# Wein.net
KiCad netlist of a schematic drawn in Altium Designer
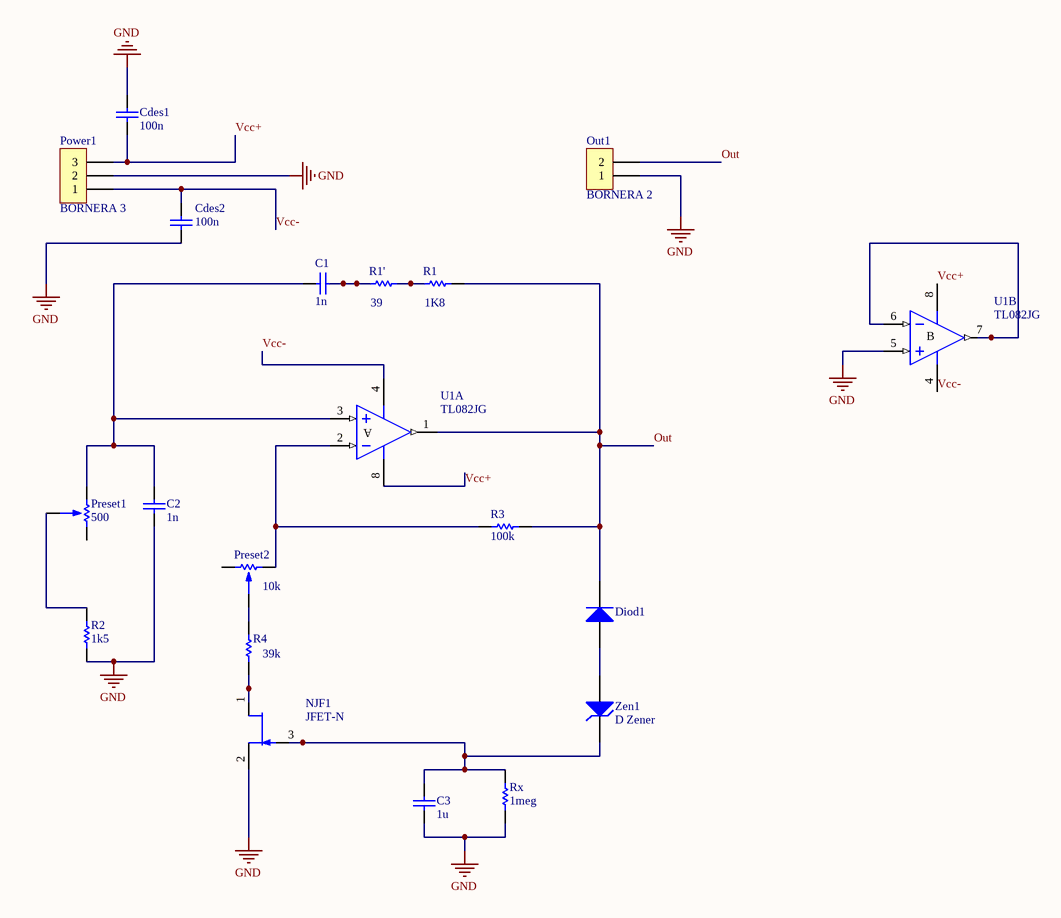
[diagram p0: Wein.SchDoc]

(export (version "E")
  (design (tool "Eeschema 10.0.6"))
  (components
    (comp (ref "C1")
      (value "1n")
      (footprint "RAD-0.3")
      (description "Capacitor")
      (fields (field (name "PUBLISHER") "Altium Limited"))
      (libsource (lib "Miscellaneous Devices") (part "Cap"))
    )
    (comp (ref "C2")
      (value "1n")
      (footprint "RAD-0.3")
      (description "Capacitor")
      (fields (field (name "PUBLISHER") "Altium Limited"))
      (libsource (lib "Miscellaneous Devices") (part "Cap"))
    )
    (comp (ref "C3")
      (value "1u")
      (footprint "RAD-0.3")
      (description "Capacitor")
      (fields (field (name "PUBLISHER") "Altium Limited"))
      (libsource (lib "Miscellaneous Devices") (part "Cap"))
    )
    (comp (ref "Cdes1")
      (value "100n")
      (footprint "RAD-0.3")
      (description "Capacitor")
      (fields (field (name "PUBLISHER") "Altium Limited"))
      (libsource (lib "Miscellaneous Devices") (part "Cap"))
    )
    (comp (ref "Cdes2")
      (value "100n")
      (footprint "RAD-0.3")
      (description "Capacitor")
      (fields (field (name "PUBLISHER") "Altium Limited"))
      (libsource (lib "Miscellaneous Devices") (part "Cap"))
    )
    (comp (ref "Diod1")
      (value "~")
      (footprint "DO-35")
      (description "High Conductance Fast Diode")
      (fields (field (name "PUBLISHER") "Altium Limited"))
      (libsource (lib "Miscellaneous Devices") (part "Diode 1N4148"))
    )
    (comp (ref "NJF1")
      (value "JFET-N")
      (footprint "TO-254-AA")
      (description "N-Channel JFET")
      (fields (field (name "PUBLISHER") "Altium Limited"))
      (libsource (lib "Miscellaneous Devices") (part "JFET-N"))
    )
    (comp (ref "Out1")
      (value "BORNERA 2")
      (footprint "BORNERA2")
      (libsource (lib "LIBEBAL") (part "BORNERA 2"))
    )
    (comp (ref "Power1")
      (value "BORNERA 3")
      (footprint "BORNERA3")
      (libsource (lib "LIBEBAL") (part "BORNERA 3"))
    )
    (comp (ref "Preset1") (value "500") (footprint "PRESET V") (libsource (lib "LIBEBAL") (part "PRESET")))
    (comp (ref "Preset2") (value "10k") (footprint "PRESET V") (libsource (lib "LIBEBAL") (part "PRESET")))
    (comp (ref "R1")
      (value "1K8")
      (footprint "AXIAL-0.3")
      (description "Resistor")
      (fields (field (name "PUBLISHER") "Altium Limited"))
      (libsource (lib "Miscellaneous Devices") (part "Res1"))
    )
    (comp (ref "R1'")
      (value "39")
      (footprint "AXIAL-0.3")
      (description "Resistor")
      (fields (field (name "PUBLISHER") "Altium Limited"))
      (libsource (lib "Miscellaneous Devices") (part "Res1"))
    )
    (comp (ref "R2")
      (value "1k5")
      (footprint "AXIAL-0.3")
      (description "Resistor")
      (fields (field (name "PUBLISHER") "Altium Limited"))
      (libsource (lib "Miscellaneous Devices") (part "Res1"))
    )
    (comp (ref "R3")
      (value "100k")
      (footprint "AXIAL-0.3")
      (description "Resistor")
      (fields (field (name "PUBLISHER") "Altium Limited"))
      (libsource (lib "Miscellaneous Devices") (part "Res1"))
    )
    (comp (ref "R4")
      (value "39k")
      (footprint "AXIAL-0.3")
      (description "Resistor")
      (fields (field (name "PUBLISHER") "Altium Limited"))
      (libsource (lib "Miscellaneous Devices") (part "Res1"))
    )
    (comp (ref "Rx")
      (value "1meg")
      (footprint "AXIAL-0.3")
      (description "Resistor")
      (fields (field (name "PUBLISHER") "Altium Limited"))
      (libsource (lib "Miscellaneous Devices") (part "Res1"))
    )
    (comp (ref "U1")
      (value "TL082JG")
      (footprint "JG008")
      (description "JFET-Input Operational Amplifier")
      (fields (field (name "PUBLISHER") "Altium Limited"))
      (libsource (lib "TI Operational Amplifier") (part "TL082JG"))
    )
    (comp (ref "Zen1")
      (value "D Zener")
      (footprint "DIODE-0.7")
      (description "Zener Diode")
      (fields (field (name "PUBLISHER") "Altium Limited"))
      (libsource (lib "Miscellaneous Devices") (part "D Zener"))
    )
  )
  (nets
    (net (code "1") (name "/Out") (class "Default")
      (node (ref "Diod1") (pin "2") (pinfunction "K_2") (pintype "passive"))
      (node (ref "Out1") (pin "2") (pinfunction "2_2") (pintype "passive"))
      (node (ref "R1") (pin "2") (pinfunction "2_2") (pintype "passive"))
      (node (ref "R3") (pin "2") (pinfunction "2_2") (pintype "passive"))
      (node (ref "U1") (pin "1") (pinfunction "OUT_1") (pintype "output"))
    )
    (net (code "2") (name "/Vcc+") (class "Default")
      (node (ref "Cdes1") (pin "1") (pinfunction "1_1") (pintype "passive"))
      (node (ref "Power1") (pin "3") (pinfunction "3_3") (pintype "passive"))
      (node (ref "U1") (pin "8") (pinfunction "V+_8") (pintype "power_in"))
    )
    (net (code "3") (name "/Vcc-") (class "Default")
      (node (ref "Cdes2") (pin "2") (pinfunction "2_2") (pintype "passive"))
      (node (ref "Power1") (pin "1") (pinfunction "1_1") (pintype "passive"))
      (node (ref "U1") (pin "4") (pinfunction "V-_4") (pintype "power_in"))
    )
    (net (code "4") (name "GND") (class "Default")
      (node (ref "C2") (pin "1") (pinfunction "1_1") (pintype "passive"))
      (node (ref "C3") (pin "1") (pinfunction "1_1") (pintype "passive"))
      (node (ref "Cdes1") (pin "2") (pinfunction "2_2") (pintype "passive"))
      (node (ref "Cdes2") (pin "1") (pinfunction "1_1") (pintype "passive"))
      (node (ref "NJF1") (pin "2") (pinfunction "S_2") (pintype "passive"))
      (node (ref "Out1") (pin "1") (pinfunction "1_1") (pintype "passive"))
      (node (ref "Power1") (pin "2") (pinfunction "2_2") (pintype "passive"))
      (node (ref "R2") (pin "1") (pinfunction "1_1") (pintype "passive"))
      (node (ref "Rx") (pin "1") (pinfunction "1_1") (pintype "passive"))
      (node (ref "U1") (pin "5") (pinfunction "IN+_5") (pintype "input"))
    )
    (net (code "5") (name "Net-(C1-Pad2)") (class "Default")
      (node (ref "C1") (pin "2") (pinfunction "2_2") (pintype "passive"))
      (node (ref "R1'") (pin "1") (pinfunction "1_1") (pintype "passive"))
    )
    (net (code "6") (name "Net-(Diod1-A)") (class "Default")
      (node (ref "Diod1") (pin "1") (pinfunction "A_1") (pintype "passive"))
      (node (ref "Zen1") (pin "1") (pinfunction "A_1") (pintype "passive"))
    )
    (net (code "7") (name "Net-(NJF1-D)") (class "Default")
      (node (ref "NJF1") (pin "1") (pinfunction "D_1") (pintype "passive"))
      (node (ref "R4") (pin "2") (pinfunction "2_2") (pintype "passive"))
    )
    (net (code "8") (name "Net-(NJF1-G)") (class "Default")
      (node (ref "C3") (pin "2") (pinfunction "2_2") (pintype "passive"))
      (node (ref "NJF1") (pin "3") (pinfunction "G_3") (pintype "passive"))
      (node (ref "Rx") (pin "2") (pinfunction "2_2") (pintype "passive"))
      (node (ref "Zen1") (pin "2") (pinfunction "K_2") (pintype "passive"))
    )
    (net (code "9") (name "Net-(Preset1-Pad2)") (class "Default")
      (node (ref "Preset1") (pin "2") (pinfunction "2_2") (pintype "passive"))
      (node (ref "R2") (pin "2") (pinfunction "2_2") (pintype "passive"))
    )
    (net (code "10") (name "Net-(Preset2-Pad2)") (class "Default")
      (node (ref "Preset2") (pin "2") (pinfunction "2_2") (pintype "passive"))
      (node (ref "R4") (pin "1") (pinfunction "1_1") (pintype "passive"))
    )
    (net (code "11") (name "Net-(R1'-Pad2)") (class "Default")
      (node (ref "R1") (pin "1") (pinfunction "1_1") (pintype "passive"))
      (node (ref "R1'") (pin "2") (pinfunction "2_2") (pintype "passive"))
    )
    (net (code "12") (name "Net-(U1A-IN+)") (class "Default")
      (node (ref "C1") (pin "1") (pinfunction "1_1") (pintype "passive"))
      (node (ref "C2") (pin "2") (pinfunction "2_2") (pintype "passive"))
      (node (ref "Preset1") (pin "3") (pinfunction "3_3") (pintype "passive"))
      (node (ref "U1") (pin "3") (pinfunction "IN+_3") (pintype "input"))
    )
    (net (code "13") (name "Net-(U1A-IN-)") (class "Default")
      (node (ref "Preset2") (pin "1") (pinfunction "1_1") (pintype "passive"))
      (node (ref "R3") (pin "1") (pinfunction "1_1") (pintype "passive"))
      (node (ref "U1") (pin "2") (pinfunction "IN-_2") (pintype "input"))
    )
    (net (code "14") (name "Net-(U1B-IN-)") (class "Default")
      (node (ref "U1") (pin "6") (pinfunction "IN-_6") (pintype "input"))
      (node (ref "U1") (pin "7") (pinfunction "OUT_7") (pintype "output"))
    )
    (net (code "15") (name "unconnected-(Preset1-Pad1)") (class "Default")
      (node (ref "Preset1") (pin "1") (pinfunction "1_1") (pintype "passive"))
    )
    (net (code "16") (name "unconnected-(Preset2-Pad3)") (class "Default")
      (node (ref "Preset2") (pin "3") (pinfunction "3_3") (pintype "passive"))
    )
  )
)
